# Table_Clock.net
KiCad netlist of a schematic drawn in Altium Designer
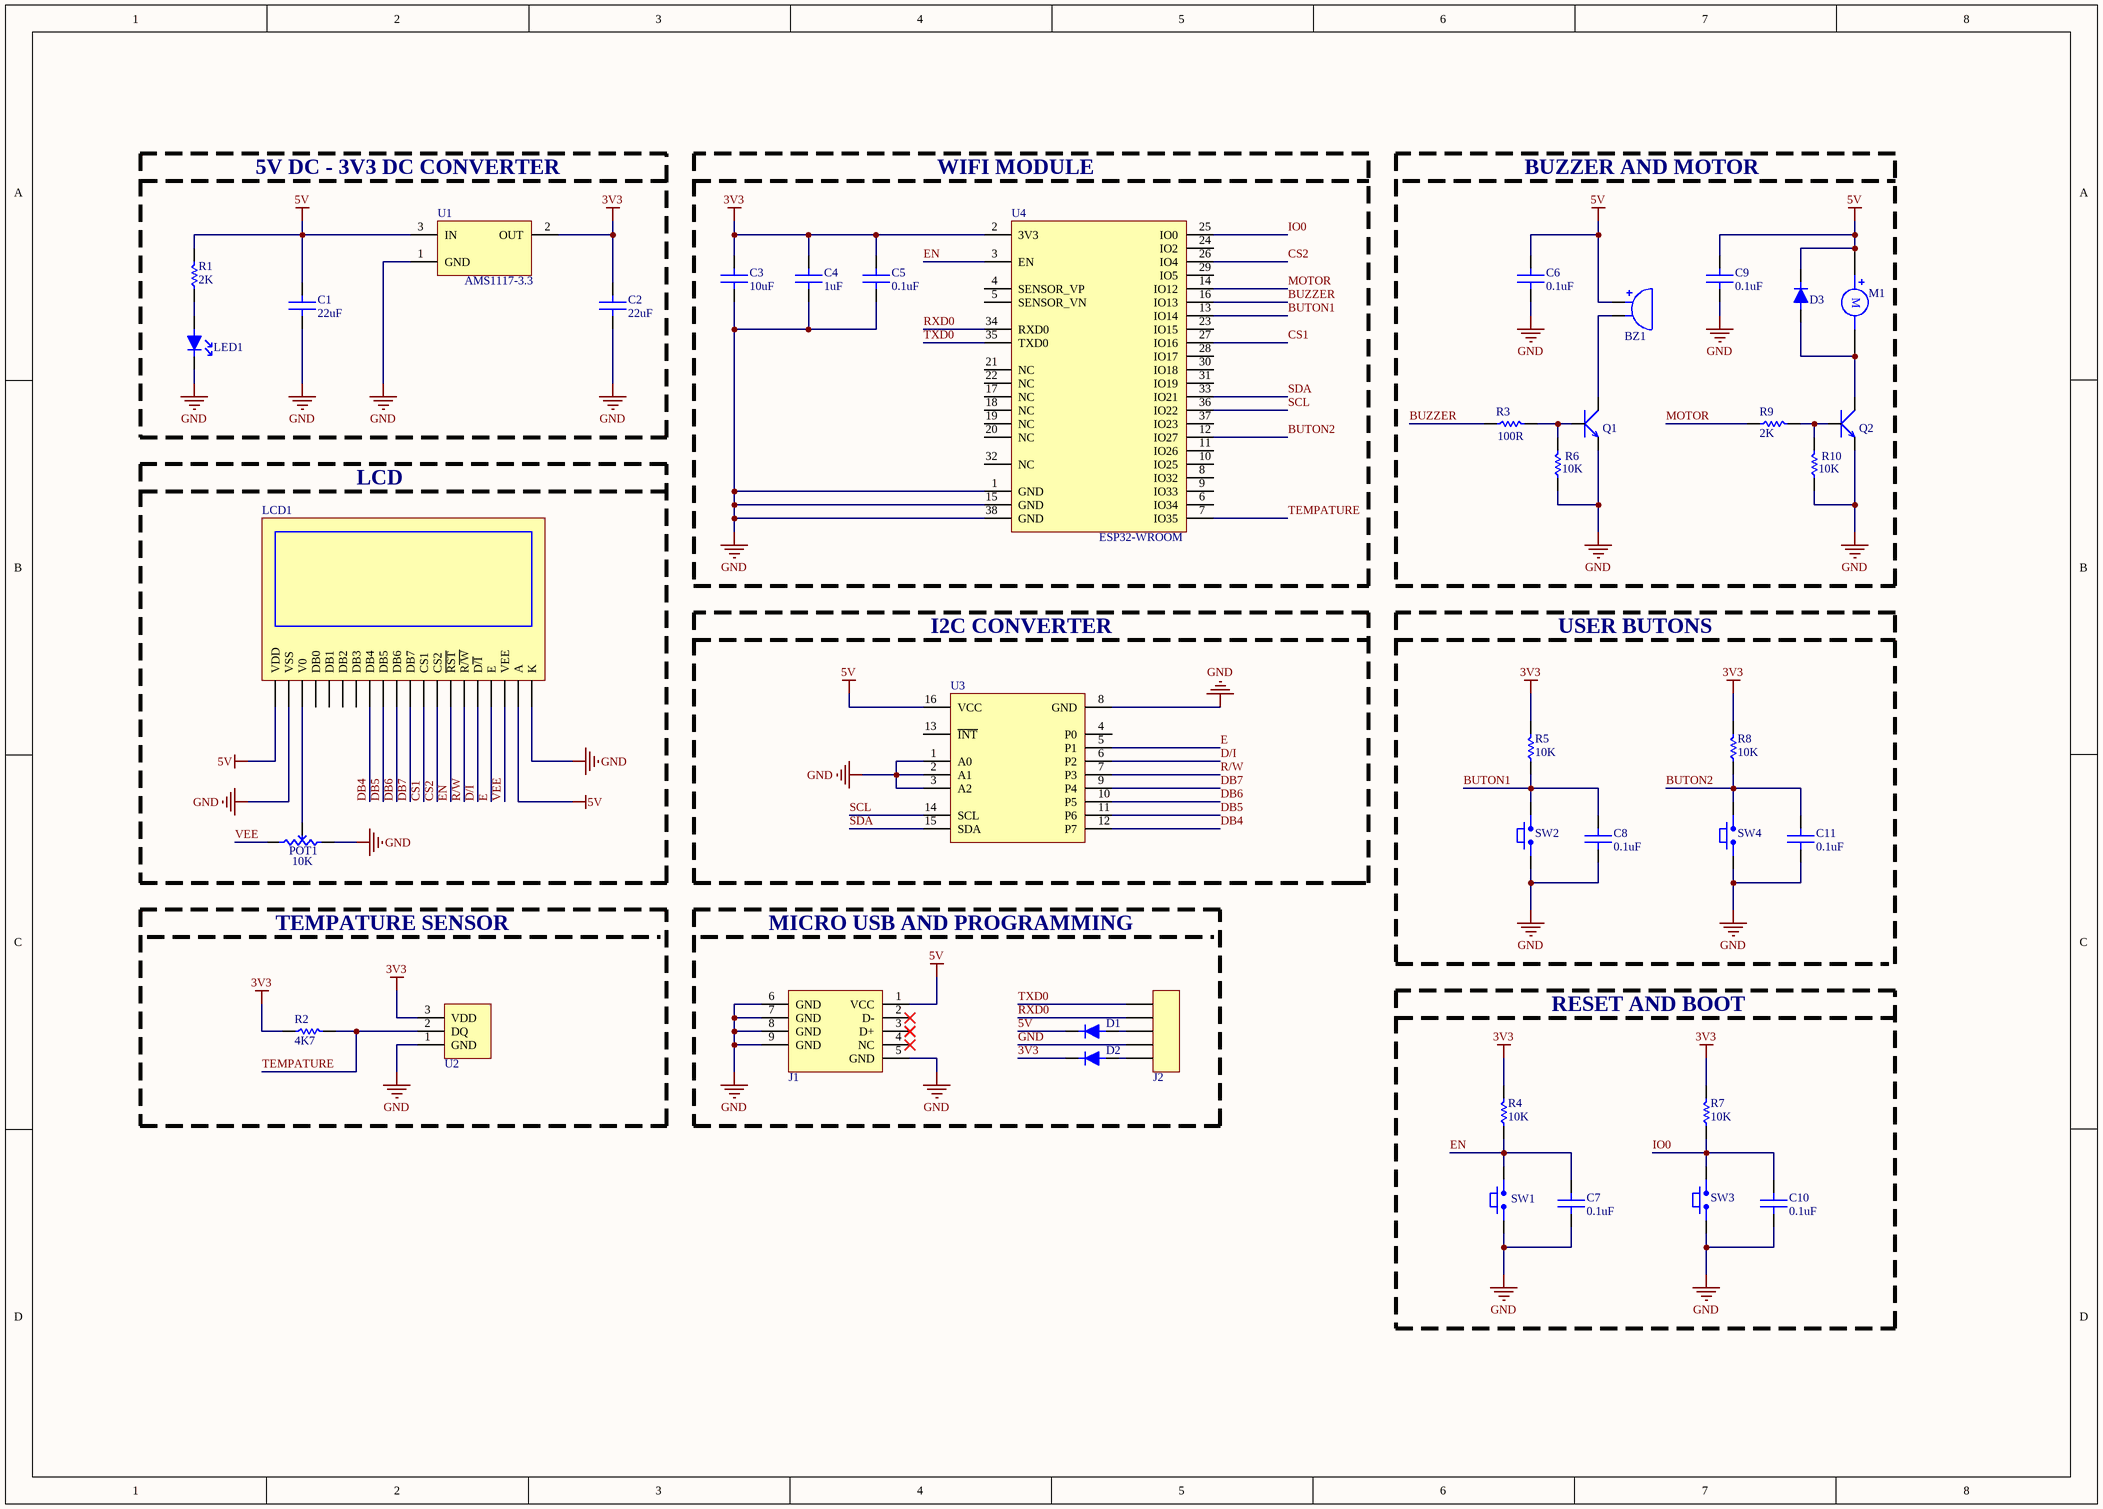
[diagram p0: Table Clock.SchDoc]

(export (version "E")
  (design (tool "Eeschema 10.0.6"))
  (components
    (comp (ref "BZ1")
      (value "CMI-9605IC-0580T")
      (footprint "BUZZER")
      (description "BUZZER MAGNETIC 5V 9.6MM TH")
      (libsource (lib "Table Clock") (part "BUZZER"))
    )
    (comp (ref "C1")
      (value "22uF")
      (footprint "CAP 0805")
      (description "CAP CER 22UF 25V X5R 0805")
      (fields (field (name "Comment") "GRM21BR61E226ME44L"))
      (libsource (lib "Table Clock") (part "CAP CER 22UF 0805"))
    )
    (comp (ref "C2")
      (value "22uF")
      (footprint "CAP 0805")
      (description "CAP CER 22UF 25V X5R 0805")
      (fields (field (name "Comment") "GRM21BR61E226ME44L"))
      (libsource (lib "Table Clock") (part "CAP CER 22UF 0805"))
    )
    (comp (ref "C3")
      (value "10uF")
      (footprint "CAP 0805")
      (description "CAP CER 10UF 25V X5R 0805")
      (fields (field (name "Comment") "CC0805KKX5R8BB106"))
      (libsource (lib "Table Clock") (part "CAP CER 10UF 0805"))
    )
    (comp (ref "C4")
      (value "1uF")
      (footprint "CAP 0805")
      (description "CAP CER 1UF 50V X7R 0805")
      (fields (field (name "Comment") "CC0805KKX7R9BB105"))
      (libsource (lib "Table Clock") (part "CAP CER 1UF 0805"))
    )
    (comp (ref "C5")
      (value "0.1uF")
      (footprint "CAP 0805")
      (description "CAP CER 0.1UF 50V X7R 0805")
      (fields (field (name "Comment") "CC0805KRX7R9BB104"))
      (libsource (lib "Table Clock") (part "CAP CER 0.1UF 0805"))
    )
    (comp (ref "C6")
      (value "0.1uF")
      (footprint "CAP 0805")
      (description "CAP CER 0.1UF 50V X7R 0805")
      (fields (field (name "Comment") "CC0805KRX7R9BB104"))
      (libsource (lib "Table Clock") (part "CAP CER 0.1UF 0805"))
    )
    (comp (ref "C7")
      (value "0.1uF")
      (footprint "CAP 0805")
      (description "CAP CER 0.1UF 50V X7R 0805")
      (fields (field (name "Comment") "CC0805KRX7R9BB104"))
      (libsource (lib "Table Clock") (part "CAP CER 0.1UF 0805"))
    )
    (comp (ref "C8")
      (value "0.1uF")
      (footprint "CAP 0805")
      (description "CAP CER 0.1UF 50V X7R 0805")
      (fields (field (name "Comment") "CC0805KRX7R9BB104"))
      (libsource (lib "Table Clock") (part "CAP CER 0.1UF 0805"))
    )
    (comp (ref "C9")
      (value "0.1uF")
      (footprint "CAP 0805")
      (description "CAP CER 0.1UF 50V X7R 0805")
      (fields (field (name "Comment") "CC0805KRX7R9BB104"))
      (libsource (lib "Table Clock") (part "CAP CER 0.1UF 0805"))
    )
    (comp (ref "C10")
      (value "0.1uF")
      (footprint "CAP 0805")
      (description "CAP CER 0.1UF 50V X7R 0805")
      (fields (field (name "Comment") "CC0805KRX7R9BB104"))
      (libsource (lib "Table Clock") (part "CAP CER 0.1UF 0805"))
    )
    (comp (ref "C11")
      (value "0.1uF")
      (footprint "CAP 0805")
      (description "CAP CER 0.1UF 50V X7R 0805")
      (fields (field (name "Comment") "CC0805KRX7R9BB104"))
      (libsource (lib "Table Clock") (part "CAP CER 0.1UF 0805"))
    )
    (comp (ref "D1")
      (value "MBR230LSFT1G")
      (footprint "DIODE")
      (description "DIODE SCHOTTKY 30V 2A")
      (libsource (lib "Table Clock") (part "DIODE SMD"))
    )
    (comp (ref "D2")
      (value "MBR230LSFT1G")
      (footprint "DIODE")
      (description "DIODE SCHOTTKY 30V 2A")
      (libsource (lib "Table Clock") (part "DIODE SMD"))
    )
    (comp (ref "D3")
      (value "MBR230LSFT1G")
      (footprint "DIODE")
      (description "DIODE SCHOTTKY 30V 2A")
      (libsource (lib "Table Clock") (part "DIODE SMD"))
    )
    (comp (ref "J1")
      (value "UJ2-MIBH-G-SMT-TR")
      (footprint "MICRO USB")
      (description "USB JACK 2.0 MICRO B TYPE 5 P")
      (libsource (lib "Table Clock") (part "MICRO USB"))
    )
    (comp (ref "J2")
      (value "61300511121")
      (footprint "HEADER 5 POS")
      (description "CONN HEADER 5POS 2.54MM")
      (libsource (lib "Table Clock") (part "HEADER 5 POS"))
    )
    (comp (ref "LCD1")
      (value "NHD-12864WG-BTFH-V#N")
      (footprint "LCD SCREEN")
      (description "GRAPHIC DISPLAY LCD TH")
      (libsource (lib "Table Clock") (part "LCD SCREEN"))
    )
    (comp (ref "LED1")
      (value "150080RS75000")
      (footprint "LED 0805")
      (description "LED RED 0805 SMD")
      (libsource (lib "Table Clock") (part "RED LED 0805"))
    )
    (comp (ref "M1")
      (value "HD-EM1003-LW15-R")
      (footprint "Motor")
      (description "HD MOTOR 3VDC 46OHM 12000RPM")
      (libsource (lib "Table Clock") (part "VIBRATION DC MOTOR"))
    )
    (comp (ref "POT1")
      (value "10K")
      (footprint "TRIMMER")
      (description "TRIMMER 10K OHM 0.5W PC PIN TOP")
      (fields (field (name "Comment") "3362P-1-103LF"))
      (libsource (lib "Table Clock") (part "TRIMMER"))
    )
    (comp (ref "Q1")
      (value "SS8050-G")
      (footprint "SOT23-3")
      (description "TRANS NPN 25V 1.5A SOT-23-3")
      (libsource (lib "Table Clock") (part "NPN TRANSISTOR"))
    )
    (comp (ref "Q2")
      (value "SS8050-G")
      (footprint "SOT23-3")
      (description "TRANS NPN 25V 1.5A SOT-23-3")
      (libsource (lib "Table Clock") (part "NPN TRANSISTOR"))
    )
    (comp (ref "R1")
      (value "2K")
      (footprint "RES 0603")
      (description "RES 2K OHM 5% 1/5W 0603")
      (fields (field (name "Comment") "CRGH0603J2K0"))
      (libsource (lib "Table Clock") (part "RES 2K OHM 0603"))
    )
    (comp (ref "R2")
      (value "4K7")
      (footprint "RES 0603")
      (description "RES 4.7K OHM 5% 1/5W 0603")
      (fields (field (name "Comment") "CRGH0603J4K7"))
      (libsource (lib "Table Clock") (part "RES 4K7 OHM 0603"))
    )
    (comp (ref "R3")
      (value "100R")
      (footprint "RES 0603")
      (description "RES 100 OHM 5% 1/5W 0603")
      (fields (field (name "Comment") "CRGH0603J100R"))
      (libsource (lib "Table Clock") (part "RES 100 OHM 0603"))
    )
    (comp (ref "R4")
      (value "10K")
      (footprint "RES 0603")
      (description "RES 10K OHM 5% 1/5W 0603")
      (fields (field (name "Comment") "CRGH0603J10K"))
      (libsource (lib "Table Clock") (part "RES 10K OHM 0603"))
    )
    (comp (ref "R5")
      (value "10K")
      (footprint "RES 0603")
      (description "RES 10K OHM 5% 1/5W 0603")
      (fields (field (name "Comment") "CRGH0603J10K"))
      (libsource (lib "Table Clock") (part "RES 10K OHM 0603"))
    )
    (comp (ref "R6")
      (value "10K")
      (footprint "RES 0603")
      (description "RES 10K OHM 5% 1/5W 0603")
      (fields (field (name "Comment") "CRGH0603J10K"))
      (libsource (lib "Table Clock") (part "RES 10K OHM 0603"))
    )
    (comp (ref "R7")
      (value "10K")
      (footprint "RES 0603")
      (description "RES 10K OHM 5% 1/5W 0603")
      (fields (field (name "Comment") "CRGH0603J10K"))
      (libsource (lib "Table Clock") (part "RES 10K OHM 0603"))
    )
    (comp (ref "R8")
      (value "10K")
      (footprint "RES 0603")
      (description "RES 10K OHM 5% 1/5W 0603")
      (fields (field (name "Comment") "CRGH0603J10K"))
      (libsource (lib "Table Clock") (part "RES 10K OHM 0603"))
    )
    (comp (ref "R9")
      (value "2K")
      (footprint "RES 0603")
      (description "RES 2K OHM 5% 1/5W 0603")
      (fields (field (name "Comment") "CRGH0603J2K0"))
      (libsource (lib "Table Clock") (part "RES 2K OHM 0603"))
    )
    (comp (ref "R10")
      (value "10K")
      (footprint "RES 0603")
      (description "RES 10K OHM 5% 1/5W 0603")
      (fields (field (name "Comment") "CRGH0603J10K"))
      (libsource (lib "Table Clock") (part "RES 10K OHM 0603"))
    )
    (comp (ref "SW1")
      (value "PTS636SM43SMTR LFS")
      (footprint "BUTTON")
      (description "SWITCH TACTILE 0.05A 12V")
      (libsource (lib "Table Clock") (part "BUTTON"))
    )
    (comp (ref "SW2")
      (value "PTS636SM50 LFS")
      (footprint "HEADER 2 POS")
      (description "SWITCH TACTILE 0.05A 12V")
      (libsource (lib "Table Clock") (part "USER BUTTON"))
    )
    (comp (ref "SW3")
      (value "PTS636SM43SMTR LFS")
      (footprint "BUTTON")
      (description "SWITCH TACTILE 0.05A 12V")
      (libsource (lib "Table Clock") (part "BUTTON"))
    )
    (comp (ref "SW4")
      (value "PTS636SM50 LFS")
      (footprint "HEADER 2 POS")
      (description "SWITCH TACTILE 0.05A 12V")
      (libsource (lib "Table Clock") (part "USER BUTTON"))
    )
    (comp (ref "U1")
      (value "AMS1117-3.3")
      (footprint "SOT 223")
      (description "IC LDO REG 3.3V 1A SOT223 SMD")
      (libsource (lib "Table Clock") (part "LDO REG 3V3 1A"))
    )
    (comp (ref "U2")
      (value "DS18B20")
      (footprint "HEADER 3 POS")
      (description "SENSOR DIGITAL -55C-125C TO92-3")
      (libsource (lib "Table Clock") (part "TEMPATURE SENSOR"))
    )
    (comp (ref "U3")
      (value "PCF8574ADWR")
      (footprint "SOIC-16")
      (description "IC XPNDR 100KHZ I2C 16SOIC")
      (libsource (lib "Table Clock") (part "I2C CONVERTER"))
    )
    (comp (ref "U4")
      (value "ESP32-WROOM")
      (footprint "ESP32")
      (description "RF TXRX MOD BT WIFI TH SMD")
      (fields (field (name "Comment") "ESP32-WROOM-32E-H4"))
      (libsource (lib "Table Clock") (part "ESP32-WROOM"))
    )
  )
  (nets
    (net (code "1") (name "/BUTON1") (class "Default")
      (node (ref "C8") (pin "2") (pintype "passive"))
      (node (ref "R5") (pin "1") (pintype "passive"))
      (node (ref "SW2") (pin "2") (pinfunction "2_2") (pintype "passive"))
      (node (ref "U4") (pin "13") (pinfunction "IO14_13") (pintype "passive"))
    )
    (net (code "2") (name "/BUTON2") (class "Default")
      (node (ref "C11") (pin "2") (pintype "passive"))
      (node (ref "R8") (pin "1") (pintype "passive"))
      (node (ref "SW4") (pin "2") (pinfunction "2_2") (pintype "passive"))
      (node (ref "U4") (pin "12") (pinfunction "IO27_12") (pintype "passive"))
    )
    (net (code "3") (name "/BUZZER") (class "Default")
      (node (ref "R3") (pin "1") (pintype "passive"))
      (node (ref "U4") (pin "16") (pinfunction "IO13_16") (pintype "passive"))
    )
    (net (code "4") (name "/CS1") (class "Default")
      (node (ref "LCD1") (pin "12") (pinfunction "CS1_12") (pintype "passive"))
      (node (ref "U4") (pin "27") (pinfunction "IO16_27") (pintype "passive"))
    )
    (net (code "5") (name "/CS2") (class "Default")
      (node (ref "LCD1") (pin "13") (pinfunction "CS2_13") (pintype "passive"))
      (node (ref "U4") (pin "26") (pinfunction "IO4_26") (pintype "passive"))
    )
    (net (code "6") (name "/DB4") (class "Default")
      (node (ref "LCD1") (pin "8") (pinfunction "DB4_8") (pintype "passive"))
      (node (ref "U3") (pin "12") (pinfunction "P7_12") (pintype "passive"))
    )
    (net (code "7") (name "/DB5") (class "Default")
      (node (ref "LCD1") (pin "9") (pinfunction "DB5_9") (pintype "passive"))
      (node (ref "U3") (pin "11") (pinfunction "P6_11") (pintype "passive"))
    )
    (net (code "8") (name "/DB6") (class "Default")
      (node (ref "LCD1") (pin "10") (pinfunction "DB6_10") (pintype "passive"))
      (node (ref "U3") (pin "10") (pinfunction "P5_10") (pintype "passive"))
    )
    (net (code "9") (name "/DB7") (class "Default")
      (node (ref "LCD1") (pin "11") (pinfunction "DB7_11") (pintype "passive"))
      (node (ref "U3") (pin "9") (pinfunction "P4_9") (pintype "passive"))
    )
    (net (code "10") (name "/D{slash}I") (class "Default")
      (node (ref "LCD1") (pin "16") (pinfunction "D~{/I}_16") (pintype "passive"))
      (node (ref "U3") (pin "6") (pinfunction "P2_6") (pintype "passive"))
    )
    (net (code "11") (name "/E") (class "Default")
      (node (ref "LCD1") (pin "17") (pinfunction "E_17") (pintype "passive"))
      (node (ref "U3") (pin "5") (pinfunction "P1_5") (pintype "passive"))
    )
    (net (code "12") (name "/EN") (class "Default")
      (node (ref "C7") (pin "2") (pintype "passive"))
      (node (ref "LCD1") (pin "14") (pinfunction "~{RST}_14") (pintype "passive"))
      (node (ref "R4") (pin "1") (pintype "passive"))
      (node (ref "SW1") (pin "2") (pinfunction "2_2") (pintype "passive"))
      (node (ref "U4") (pin "3") (pinfunction "EN_3") (pintype "passive"))
    )
    (net (code "13") (name "/IO0") (class "Default")
      (node (ref "C10") (pin "1") (pintype "passive"))
      (node (ref "R7") (pin "1") (pintype "passive"))
      (node (ref "SW3") (pin "2") (pinfunction "2_2") (pintype "passive"))
      (node (ref "U4") (pin "25") (pinfunction "IO0_25") (pintype "passive"))
    )
    (net (code "14") (name "/MOTOR") (class "Default")
      (node (ref "R9") (pin "1") (pintype "passive"))
      (node (ref "U4") (pin "14") (pinfunction "IO12_14") (pintype "passive"))
    )
    (net (code "15") (name "/RXD0") (class "Default")
      (node (ref "J2") (pin "2") (pintype "passive"))
      (node (ref "U4") (pin "34") (pinfunction "RXD0_34") (pintype "passive"))
    )
    (net (code "16") (name "/R{slash}W") (class "Default")
      (node (ref "LCD1") (pin "15") (pinfunction "R~{/W}_15") (pintype "passive"))
      (node (ref "U3") (pin "7") (pinfunction "P3_7") (pintype "passive"))
    )
    (net (code "17") (name "/SCL") (class "Default")
      (node (ref "U3") (pin "14") (pinfunction "SCL_14") (pintype "passive"))
      (node (ref "U4") (pin "36") (pinfunction "IO22_36") (pintype "passive"))
    )
    (net (code "18") (name "/SDA") (class "Default")
      (node (ref "U3") (pin "15") (pinfunction "SDA_15") (pintype "passive"))
      (node (ref "U4") (pin "33") (pinfunction "IO21_33") (pintype "passive"))
    )
    (net (code "19") (name "/TEMPATURE") (class "Default")
      (node (ref "R2") (pin "2") (pintype "passive"))
      (node (ref "U2") (pin "2") (pinfunction "DQ_2") (pintype "passive"))
      (node (ref "U4") (pin "7") (pinfunction "IO35_7") (pintype "passive"))
    )
    (net (code "20") (name "/TXD0") (class "Default")
      (node (ref "J2") (pin "1") (pintype "passive"))
      (node (ref "U4") (pin "35") (pinfunction "TXD0_35") (pintype "passive"))
    )
    (net (code "21") (name "/VEE") (class "Default")
      (node (ref "LCD1") (pin "18") (pinfunction "VEE_18") (pintype "passive"))
      (node (ref "POT1") (pin "1") (pintype "passive"))
    )
    (net (code "22") (name "3V3") (class "Default")
      (node (ref "C2") (pin "2") (pintype "passive"))
      (node (ref "C3") (pin "2") (pintype "passive"))
      (node (ref "C4") (pin "2") (pintype "passive"))
      (node (ref "C5") (pin "2") (pintype "passive"))
      (node (ref "D2") (pin "2") (pinfunction "2_2") (pintype "passive"))
      (node (ref "R2") (pin "1") (pintype "passive"))
      (node (ref "R4") (pin "2") (pintype "passive"))
      (node (ref "R5") (pin "2") (pintype "passive"))
      (node (ref "R7") (pin "2") (pintype "passive"))
      (node (ref "R8") (pin "2") (pintype "passive"))
      (node (ref "U1") (pin "2") (pinfunction "OUT_2") (pintype "passive"))
      (node (ref "U2") (pin "3") (pinfunction "VDD_3") (pintype "passive"))
      (node (ref "U4") (pin "2") (pinfunction "3V3_2") (pintype "passive"))
    )
    (net (code "23") (name "5V") (class "Default")
      (node (ref "BZ1") (pin "1") (pintype "passive"))
      (node (ref "C1") (pin "2") (pintype "passive"))
      (node (ref "C6") (pin "2") (pintype "passive"))
      (node (ref "C9") (pin "2") (pintype "passive"))
      (node (ref "D1") (pin "2") (pinfunction "2_2") (pintype "passive"))
      (node (ref "D3") (pin "2") (pinfunction "2_2") (pintype "passive"))
      (node (ref "J1") (pin "1") (pinfunction "VCC_1") (pintype "passive"))
      (node (ref "LCD1") (pin "1") (pinfunction "VDD_1") (pintype "passive"))
      (node (ref "LCD1") (pin "19") (pinfunction "A_19") (pintype "passive"))
      (node (ref "M1") (pin "1") (pinfunction "1_1") (pintype "passive"))
      (node (ref "R1") (pin "2") (pintype "passive"))
      (node (ref "U1") (pin "3") (pinfunction "IN_3") (pintype "passive"))
      (node (ref "U3") (pin "16") (pinfunction "VCC_16") (pintype "power_in"))
    )
    (net (code "24") (name "GND") (class "Default")
      (node (ref "C1") (pin "1") (pintype "passive"))
      (node (ref "C10") (pin "2") (pintype "passive"))
      (node (ref "C11") (pin "1") (pintype "passive"))
      (node (ref "C2") (pin "1") (pintype "passive"))
      (node (ref "C3") (pin "1") (pintype "passive"))
      (node (ref "C4") (pin "1") (pintype "passive"))
      (node (ref "C5") (pin "1") (pintype "passive"))
      (node (ref "C6") (pin "1") (pintype "passive"))
      (node (ref "C7") (pin "1") (pintype "passive"))
      (node (ref "C8") (pin "1") (pintype "passive"))
      (node (ref "C9") (pin "1") (pintype "passive"))
      (node (ref "J1") (pin "5") (pinfunction "GND_5") (pintype "passive"))
      (node (ref "J1") (pin "6") (pinfunction "GND_6") (pintype "passive"))
      (node (ref "J1") (pin "7") (pinfunction "GND_7") (pintype "passive"))
      (node (ref "J1") (pin "8") (pinfunction "GND_8") (pintype "passive"))
      (node (ref "J1") (pin "9") (pinfunction "GND_9") (pintype "passive"))
      (node (ref "J2") (pin "4") (pintype "passive"))
      (node (ref "LCD1") (pin "2") (pinfunction "VSS_2") (pintype "passive"))
      (node (ref "LCD1") (pin "20") (pinfunction "K_20") (pintype "passive"))
      (node (ref "LED1") (pin "2") (pintype "passive"))
      (node (ref "POT1") (pin "3") (pintype "passive"))
      (node (ref "Q1") (pin "2") (pintype "passive"))
      (node (ref "Q2") (pin "2") (pintype "passive"))
      (node (ref "R10") (pin "1") (pintype "passive"))
      (node (ref "R6") (pin "1") (pintype "passive"))
      (node (ref "SW1") (pin "1") (pinfunction "1_1") (pintype "passive"))
      (node (ref "SW2") (pin "1") (pinfunction "1_1") (pintype "passive"))
      (node (ref "SW3") (pin "1") (pinfunction "1_1") (pintype "passive"))
      (node (ref "SW4") (pin "1") (pinfunction "1_1") (pintype "passive"))
      (node (ref "U1") (pin "1") (pinfunction "GND_1") (pintype "passive"))
      (node (ref "U2") (pin "1") (pinfunction "GND_1") (pintype "passive"))
      (node (ref "U3") (pin "1") (pinfunction "A0_1") (pintype "passive"))
      (node (ref "U3") (pin "2") (pinfunction "A1_2") (pintype "passive"))
      (node (ref "U3") (pin "3") (pinfunction "A2_3") (pintype "passive"))
      (node (ref "U3") (pin "8") (pinfunction "GND_8") (pintype "power_in"))
      (node (ref "U4") (pin "1") (pinfunction "GND_1") (pintype "passive"))
      (node (ref "U4") (pin "15") (pinfunction "GND_15") (pintype "passive"))
      (node (ref "U4") (pin "38") (pinfunction "GND_38") (pintype "passive"))
    )
    (net (code "25") (name "Net-(BZ1-Pad2)") (class "Default")
      (node (ref "BZ1") (pin "2") (pintype "passive"))
      (node (ref "Q1") (pin "3") (pintype "passive"))
    )
    (net (code "26") (name "Net-(D1-Pad1)") (class "Default")
      (node (ref "D1") (pin "1") (pinfunction "1_1") (pintype "passive"))
      (node (ref "J2") (pin "3") (pintype "passive"))
    )
    (net (code "27") (name "Net-(D2-Pad1)") (class "Default")
      (node (ref "D2") (pin "1") (pinfunction "1_1") (pintype "passive"))
      (node (ref "J2") (pin "5") (pintype "passive"))
    )
    (net (code "28") (name "Net-(D3-Pad1)") (class "Default")
      (node (ref "D3") (pin "1") (pinfunction "1_1") (pintype "passive"))
      (node (ref "M1") (pin "2") (pinfunction "2_2") (pintype "passive"))
      (node (ref "Q2") (pin "3") (pintype "passive"))
    )
    (net (code "29") (name "Net-(LCD1-V0)") (class "Default")
      (node (ref "LCD1") (pin "3") (pinfunction "V0_3") (pintype "passive"))
      (node (ref "POT1") (pin "2") (pintype "passive"))
    )
    (net (code "30") (name "Net-(LED1-Pad1)") (class "Default")
      (node (ref "LED1") (pin "1") (pintype "passive"))
      (node (ref "R1") (pin "1") (pintype "passive"))
    )
    (net (code "31") (name "Net-(Q1-Pad1)") (class "Default")
      (node (ref "Q1") (pin "1") (pintype "passive"))
      (node (ref "R3") (pin "2") (pintype "passive"))
      (node (ref "R6") (pin "2") (pintype "passive"))
    )
    (net (code "32") (name "Net-(Q2-Pad1)") (class "Default")
      (node (ref "Q2") (pin "1") (pintype "passive"))
      (node (ref "R10") (pin "2") (pintype "passive"))
      (node (ref "R9") (pin "2") (pintype "passive"))
    )
    (net (code "33") (name "unconnected-(J1-D+-Pad3)") (class "Default")
      (node (ref "J1") (pin "3") (pinfunction "D+_3") (pintype "passive+no_connect"))
    )
    (net (code "34") (name "unconnected-(J1-D--Pad2)") (class "Default")
      (node (ref "J1") (pin "2") (pinfunction "D-_2") (pintype "passive+no_connect"))
    )
    (net (code "35") (name "unconnected-(J1-NC-Pad4)") (class "Default")
      (node (ref "J1") (pin "4") (pinfunction "NC_4") (pintype "passive+no_connect"))
    )
    (net (code "36") (name "unconnected-(LCD1-DB0-Pad4)") (class "Default")
      (node (ref "LCD1") (pin "4") (pinfunction "DB0_4") (pintype "passive"))
    )
    (net (code "37") (name "unconnected-(LCD1-DB1-Pad5)") (class "Default")
      (node (ref "LCD1") (pin "5") (pinfunction "DB1_5") (pintype "passive"))
    )
    (net (code "38") (name "unconnected-(LCD1-DB2-Pad6)") (class "Default")
      (node (ref "LCD1") (pin "6") (pinfunction "DB2_6") (pintype "passive"))
    )
    (net (code "39") (name "unconnected-(LCD1-DB3-Pad7)") (class "Default")
      (node (ref "LCD1") (pin "7") (pinfunction "DB3_7") (pintype "passive"))
    )
    (net (code "40") (name "unconnected-(U3-P0-Pad4)") (class "Default")
      (node (ref "U3") (pin "4") (pinfunction "P0_4") (pintype "passive"))
    )
    (net (code "41") (name "unconnected-(U3-~{INT}-Pad13)") (class "Default")
      (node (ref "U3") (pin "13") (pinfunction "~{INT}_13") (pintype "passive"))
    )
    (net (code "42") (name "unconnected-(U4-IO2-Pad24)") (class "Default")
      (node (ref "U4") (pin "24") (pinfunction "IO2_24") (pintype "passive"))
    )
    (net (code "43") (name "unconnected-(U4-IO5-Pad29)") (class "Default")
      (node (ref "U4") (pin "29") (pinfunction "IO5_29") (pintype "passive"))
    )
    (net (code "44") (name "unconnected-(U4-IO15-Pad23)") (class "Default")
      (node (ref "U4") (pin "23") (pinfunction "IO15_23") (pintype "passive"))
    )
    (net (code "45") (name "unconnected-(U4-IO17-Pad28)") (class "Default")
      (node (ref "U4") (pin "28") (pinfunction "IO17_28") (pintype "passive"))
    )
    (net (code "46") (name "unconnected-(U4-IO18-Pad30)") (class "Default")
      (node (ref "U4") (pin "30") (pinfunction "IO18_30") (pintype "passive"))
    )
    (net (code "47") (name "unconnected-(U4-IO19-Pad31)") (class "Default")
      (node (ref "U4") (pin "31") (pinfunction "IO19_31") (pintype "passive"))
    )
    (net (code "48") (name "unconnected-(U4-IO23-Pad37)") (class "Default")
      (node (ref "U4") (pin "37") (pinfunction "IO23_37") (pintype "passive"))
    )
    (net (code "49") (name "unconnected-(U4-IO25-Pad10)") (class "Default")
      (node (ref "U4") (pin "10") (pinfunction "IO25_10") (pintype "passive"))
    )
    (net (code "50") (name "unconnected-(U4-IO26-Pad11)") (class "Default")
      (node (ref "U4") (pin "11") (pinfunction "IO26_11") (pintype "passive"))
    )
    (net (code "51") (name "unconnected-(U4-IO32-Pad8)") (class "Default")
      (node (ref "U4") (pin "8") (pinfunction "IO32_8") (pintype "passive"))
    )
    (net (code "52") (name "unconnected-(U4-IO33-Pad9)") (class "Default")
      (node (ref "U4") (pin "9") (pinfunction "IO33_9") (pintype "passive"))
    )
    (net (code "53") (name "unconnected-(U4-IO34-Pad6)") (class "Default")
      (node (ref "U4") (pin "6") (pinfunction "IO34_6") (pintype "passive"))
    )
    (net (code "54") (name "unconnected-(U4-NC-Pad17)") (class "Default")
      (node (ref "U4") (pin "17") (pinfunction "NC_17") (pintype "passive"))
    )
    (net (code "55") (name "unconnected-(U4-NC-Pad18)") (class "Default")
      (node (ref "U4") (pin "18") (pinfunction "NC_18") (pintype "passive"))
    )
    (net (code "56") (name "unconnected-(U4-NC-Pad19)") (class "Default")
      (node (ref "U4") (pin "19") (pinfunction "NC_19") (pintype "passive"))
    )
    (net (code "57") (name "unconnected-(U4-NC-Pad20)") (class "Default")
      (node (ref "U4") (pin "20") (pinfunction "NC_20") (pintype "passive"))
    )
    (net (code "58") (name "unconnected-(U4-NC-Pad21)") (class "Default")
      (node (ref "U4") (pin "21") (pinfunction "NC_21") (pintype "passive"))
    )
    (net (code "59") (name "unconnected-(U4-NC-Pad22)") (class "Default")
      (node (ref "U4") (pin "22") (pinfunction "NC_22") (pintype "passive"))
    )
    (net (code "60") (name "unconnected-(U4-NC-Pad32)") (class "Default")
      (node (ref "U4") (pin "32") (pinfunction "NC_32") (pintype "passive"))
    )
    (net (code "61") (name "unconnected-(U4-SENSOR_VN-Pad5)") (class "Default")
      (node (ref "U4") (pin "5") (pinfunction "SENSOR_VN_5") (pintype "passive"))
    )
    (net (code "62") (name "unconnected-(U4-SENSOR_VP-Pad4)") (class "Default")
      (node (ref "U4") (pin "4") (pinfunction "SENSOR_VP_4") (pintype "passive"))
    )
  )
)
